# VCO_4046_with_low_pass_filter.net
KiCad netlist of a schematic drawn in EasyEDA
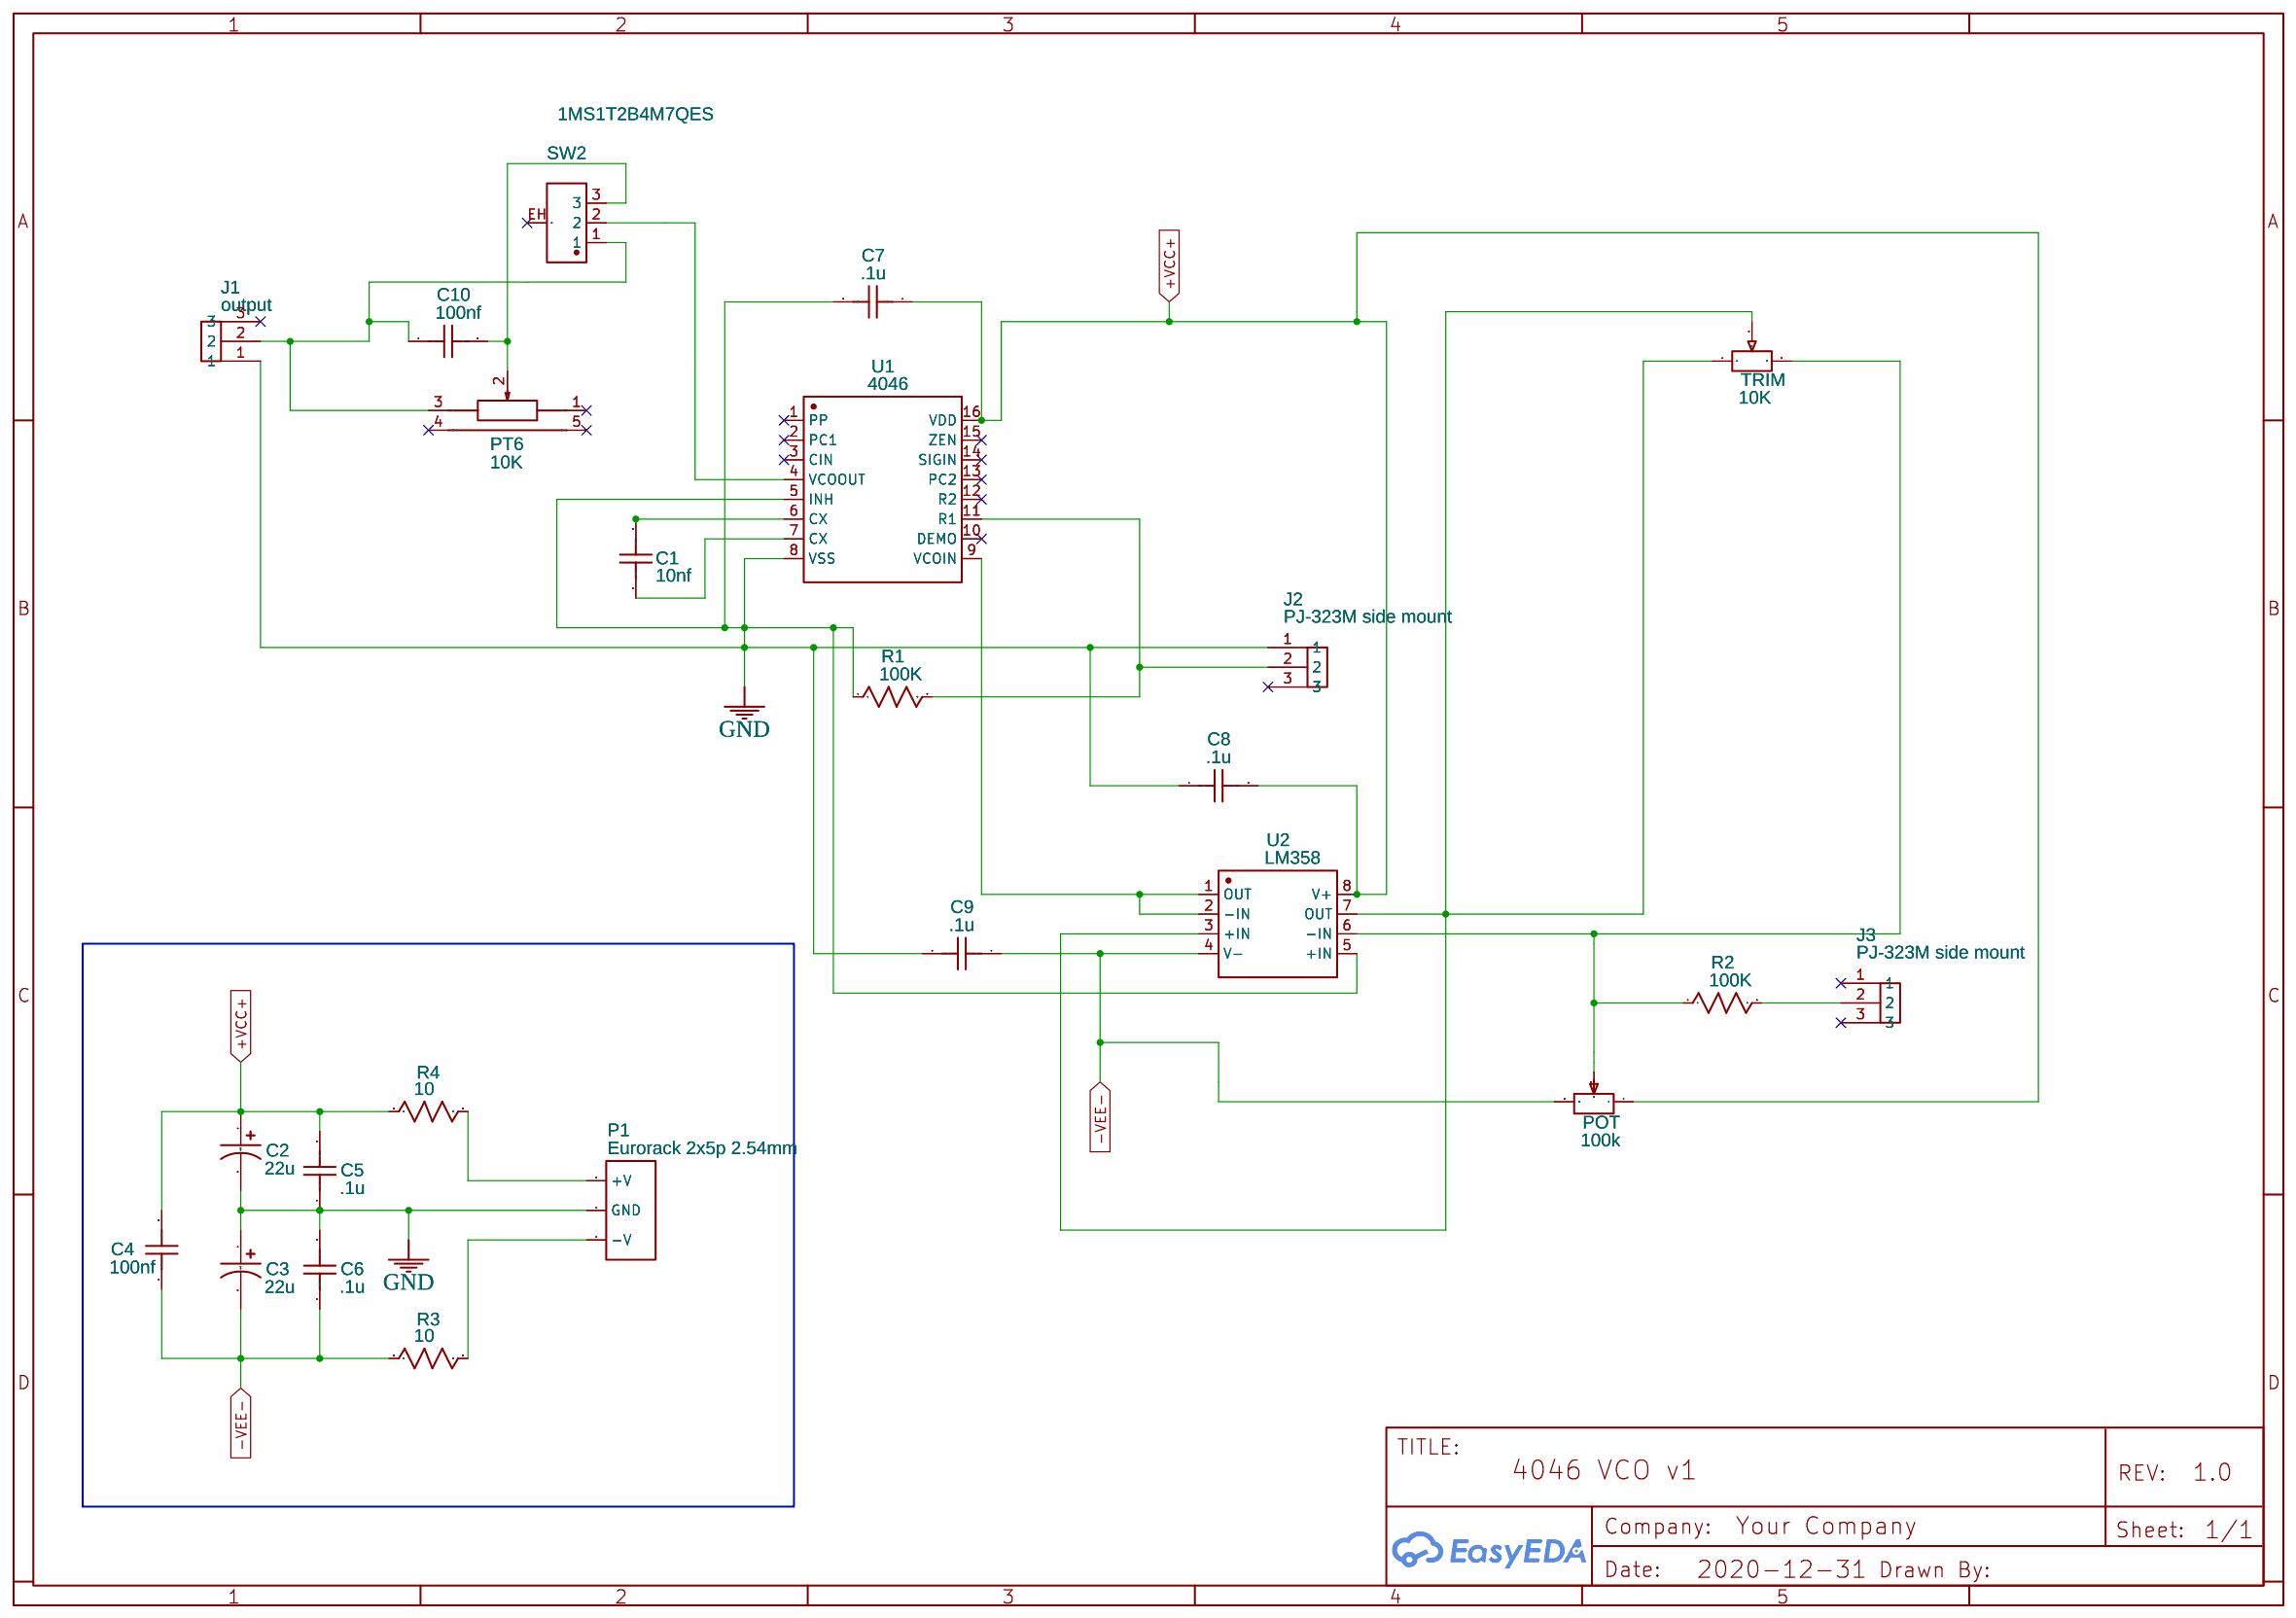
[diagram p0: schematic sheet]

(export (version "E")
  (design (tool "Eeschema 10.0.6"))
  (components
    (comp (ref "C1") (value "10nf") (libsource (lib "") (part "C_RAD-0.1_US")))
    (comp (ref "C2") (value "22u") (libsource (lib "") (part "CE_TH_D5.0×F2.0_US")))
    (comp (ref "C3") (value "22u") (libsource (lib "") (part "CE_TH_D5.0×F2.0_US")))
    (comp (ref "C4") (value "100nf") (libsource (lib "") (part "C_RAD-0.1_US")))
    (comp (ref "C5") (value ".1u") (libsource (lib "") (part "C_RAD-0.1_US")))
    (comp (ref "C6") (value ".1u") (libsource (lib "") (part "C_RAD-0.1_US")))
    (comp (ref "C7") (value ".1u") (libsource (lib "") (part "C_RAD-0.1_US_2")))
    (comp (ref "C8") (value ".1u") (libsource (lib "") (part "C_RAD-0.1_US_1")))
    (comp (ref "C9") (value ".1u") (libsource (lib "") (part "C_RAD-0.1_US_2")))
    (comp (ref "C10") (value "100nf") (libsource (lib "") (part "C_RAD-0.1_US_1")))
    (comp (ref "J1")
      (value "output")
      (fields (field (name "BOM_Manufacturer Part") "PJ-323M"))
      (libsource (lib "") (part "PJ-323M side mount"))
    )
    (comp (ref "J2")
      (value "PJ-323M side mount")
      (fields (field (name "BOM_Manufacturer Part") "PJ-323M"))
      (libsource (lib "") (part "PJ-323M side mount_1"))
    )
    (comp (ref "J3")
      (value "PJ-323M side mount")
      (fields (field (name "BOM_Manufacturer Part") "PJ-323M"))
      (libsource (lib "") (part "PJ-323M side mount_1"))
    )
    (comp (ref "P1")
      (value "Eurorack 2x5p 2.54mm")
      (fields
        (field (name "BOM_Manufacturer Part") "IDC Box 2.54mm 2X5P")
        (field (name "BOM_Supplier Part") "C5665")
      )
      (libsource (lib "") (part "Eurorack 2x5p 2.54mm"))
    )
    (comp (ref "POT")
      (value "100k")
      (fields
        (field (name "BOM_Manufacturer Part") "PTV09A-2020F-B103")
        (field (name "BOM_Supplier Part") "C370978")
      )
      (libsource (lib "") (part "RK1631110U1Q"))
    )
    (comp (ref "PT6")
      (value "10K")
      (fields
        (field (name "BOM_Manufacturer Part") "RK09K1110A0J")
        (field (name "BOM_Supplier Part") "C209767")
      )
      (libsource (lib "") (part "RK09K1110A0J"))
    )
    (comp (ref "R1") (value "100K") (libsource (lib "") (part "R_AXIAL-0.5_US")))
    (comp (ref "R2") (value "100K") (libsource (lib "") (part "R_AXIAL-0.5_US")))
    (comp (ref "R3") (value "10") (libsource (lib "") (part "R_AXIAL-0.5_US")))
    (comp (ref "R4") (value "10") (libsource (lib "") (part "R_AXIAL-0.5_US")))
    (comp (ref "SW2")
      (value "1MS1T2B4M7QES")
      (fields (field (name "BOM_Supplier Part") "C496157"))
      (libsource (lib "") (part "1MS1T2B4M7QES"))
    )
    (comp (ref "TRIM")
      (value "10K")
      (fields
        (field (name "BOM_Manufacturer Part") "3386P-1-103")
        (field (name "BOM_Supplier Part") "C118953")
      )
      (libsource (lib "") (part "3386P-1-103_C118953"))
    )
    (comp (ref "U1") (value "4046") (libsource (lib "") (part "4046")))
    (comp (ref "U2") (value "LM358") (libsource (lib "") (part "LM358")))
  )
  (nets
    (net (code "1") (name "+VCC+") (class "Default")
      (node (ref "C2") (pin "1") (pinfunction "1_1") (pintype "unspecified"))
      (node (ref "C4") (pin "2") (pinfunction "2_2") (pintype "unspecified"))
      (node (ref "C5") (pin "2") (pinfunction "2_2") (pintype "unspecified"))
      (node (ref "C7") (pin "1") (pinfunction "1_1") (pintype "unspecified"))
      (node (ref "C8") (pin "2") (pinfunction "2_2") (pintype "unspecified"))
      (node (ref "POT") (pin "1") (pinfunction "1_1") (pintype "input"))
      (node (ref "R4") (pin "1") (pinfunction "1_1") (pintype "unspecified"))
      (node (ref "U1") (pin "16") (pinfunction "VDD_16") (pintype "unspecified"))
      (node (ref "U2") (pin "8") (pinfunction "V+_8") (pintype "unspecified"))
    )
    (net (code "2") (name "-VEE-") (class "Default")
      (node (ref "C3") (pin "2") (pinfunction "2_2") (pintype "unspecified"))
      (node (ref "C4") (pin "1") (pinfunction "1_1") (pintype "unspecified"))
      (node (ref "C6") (pin "1") (pinfunction "1_1") (pintype "unspecified"))
      (node (ref "C9") (pin "1") (pinfunction "1_1") (pintype "unspecified"))
      (node (ref "POT") (pin "3") (pinfunction "3_3") (pintype "input"))
      (node (ref "R3") (pin "1") (pinfunction "1_1") (pintype "unspecified"))
      (node (ref "U2") (pin "4") (pinfunction "V-_4") (pintype "unspecified"))
    )
    (net (code "3") (name "GND") (class "Default")
      (node (ref "C2") (pin "2") (pinfunction "2_2") (pintype "unspecified"))
      (node (ref "C3") (pin "1") (pinfunction "1_1") (pintype "unspecified"))
      (node (ref "C5") (pin "1") (pinfunction "1_1") (pintype "unspecified"))
      (node (ref "C6") (pin "2") (pinfunction "2_2") (pintype "unspecified"))
      (node (ref "C7") (pin "2") (pinfunction "2_2") (pintype "unspecified"))
      (node (ref "C8") (pin "1") (pinfunction "1_1") (pintype "unspecified"))
      (node (ref "C9") (pin "2") (pinfunction "2_2") (pintype "unspecified"))
      (node (ref "J1") (pin "1") (pinfunction "1_1") (pintype "unspecified"))
      (node (ref "J2") (pin "1") (pinfunction "1_1") (pintype "unspecified"))
      (node (ref "P1") (pin "2") (pinfunction "GND_2") (pintype "unspecified"))
      (node (ref "R1") (pin "1") (pinfunction "1_1") (pintype "unspecified"))
      (node (ref "U1") (pin "5") (pinfunction "INH_5") (pintype "unspecified"))
      (node (ref "U1") (pin "8") (pinfunction "VSS_8") (pintype "unspecified"))
      (node (ref "U2") (pin "5") (pinfunction "+IN_5") (pintype "unspecified"))
    )
    (net (code "4") (name "Net-(C1-Pad1)") (class "Default")
      (node (ref "C1") (pin "1") (pinfunction "1_1") (pintype "unspecified"))
      (node (ref "U1") (pin "7") (pinfunction "CX_7") (pintype "unspecified"))
    )
    (net (code "5") (name "Net-(C1-Pad2)") (class "Default")
      (node (ref "C1") (pin "2") (pinfunction "2_2") (pintype "unspecified"))
      (node (ref "U1") (pin "6") (pinfunction "CX_6") (pintype "unspecified"))
    )
    (net (code "6") (name "Net-(C10-Pad1)") (class "Default")
      (node (ref "C10") (pin "1") (pinfunction "1_1") (pintype "unspecified"))
      (node (ref "J1") (pin "2") (pinfunction "2_2") (pintype "unspecified"))
      (node (ref "PT6") (pin "3") (pinfunction "3_3") (pintype "unspecified"))
      (node (ref "SW2") (pin "1") (pinfunction "1_1") (pintype "unspecified"))
    )
    (net (code "7") (name "Net-(C10-Pad2)") (class "Default")
      (node (ref "C10") (pin "2") (pinfunction "2_2") (pintype "unspecified"))
      (node (ref "PT6") (pin "2") (pinfunction "2_2") (pintype "unspecified"))
      (node (ref "SW2") (pin "3") (pinfunction "3_3") (pintype "unspecified"))
    )
    (net (code "8") (name "Net-(J3-Pad2)") (class "Default")
      (node (ref "J3") (pin "2") (pinfunction "2_2") (pintype "unspecified"))
      (node (ref "R2") (pin "2") (pinfunction "2_2") (pintype "unspecified"))
    )
    (net (code "9") (name "Net-(P1-+V)") (class "Default")
      (node (ref "P1") (pin "3") (pinfunction "+V_3") (pintype "unspecified"))
      (node (ref "R4") (pin "2") (pinfunction "2_2") (pintype "unspecified"))
    )
    (net (code "10") (name "Net-(P1--V)") (class "Default")
      (node (ref "P1") (pin "1") (pinfunction "-V_1") (pintype "unspecified"))
      (node (ref "R3") (pin "2") (pinfunction "2_2") (pintype "unspecified"))
    )
    (net (code "11") (name "Net-(POT-Pad2)") (class "Default")
      (node (ref "POT") (pin "2") (pinfunction "2_2") (pintype "input"))
      (node (ref "R2") (pin "1") (pinfunction "1_1") (pintype "unspecified"))
      (node (ref "TRIM") (pin "3") (pinfunction "3_3") (pintype "input"))
      (node (ref "U2") (pin "6") (pinfunction "-IN_6") (pintype "unspecified"))
    )
    (net (code "12") (name "Net-(TRIM-Pad1)") (class "Default")
      (node (ref "TRIM") (pin "1") (pinfunction "1_1") (pintype "input"))
      (node (ref "TRIM") (pin "2") (pinfunction "2_2") (pintype "input"))
      (node (ref "U2") (pin "3") (pinfunction "+IN_3") (pintype "unspecified"))
      (node (ref "U2") (pin "7") (pinfunction "OUT_7") (pintype "unspecified"))
    )
    (net (code "13") (name "Net-(U1-R1)") (class "Default")
      (node (ref "J2") (pin "2") (pinfunction "2_2") (pintype "unspecified"))
      (node (ref "R1") (pin "2") (pinfunction "2_2") (pintype "unspecified"))
      (node (ref "U1") (pin "11") (pinfunction "R1_11") (pintype "unspecified"))
    )
    (net (code "14") (name "Net-(U1-VCOIN)") (class "Default")
      (node (ref "U1") (pin "9") (pinfunction "VCOIN_9") (pintype "unspecified"))
      (node (ref "U2") (pin "1") (pinfunction "OUT_1") (pintype "unspecified"))
      (node (ref "U2") (pin "2") (pinfunction "-IN_2") (pintype "unspecified"))
    )
    (net (code "15") (name "Net-(U1-VCOOUT)") (class "Default")
      (node (ref "SW2") (pin "2") (pinfunction "2_2") (pintype "unspecified"))
      (node (ref "U1") (pin "4") (pinfunction "VCOOUT_4") (pintype "unspecified"))
    )
    (net (code "16") (name "unconnected-(J1-Pad3)") (class "Default")
      (node (ref "J1") (pin "3") (pinfunction "3_3") (pintype "unspecified+no_connect"))
    )
    (net (code "17") (name "unconnected-(J2-Pad3)") (class "Default")
      (node (ref "J2") (pin "3") (pinfunction "3_3") (pintype "unspecified+no_connect"))
    )
    (net (code "18") (name "unconnected-(J3-Pad1)") (class "Default")
      (node (ref "J3") (pin "1") (pinfunction "1_1") (pintype "unspecified+no_connect"))
    )
    (net (code "19") (name "unconnected-(J3-Pad3)") (class "Default")
      (node (ref "J3") (pin "3") (pinfunction "3_3") (pintype "unspecified+no_connect"))
    )
    (net (code "20") (name "unconnected-(PT6-EH-Pad4)") (class "Default")
      (node (ref "PT6") (pin "4") (pinfunction "EH_4") (pintype "unspecified+no_connect"))
    )
    (net (code "21") (name "unconnected-(PT6-EH-Pad5)") (class "Default")
      (node (ref "PT6") (pin "5") (pinfunction "EH_5") (pintype "unspecified+no_connect"))
    )
    (net (code "22") (name "unconnected-(PT6-Pad1)") (class "Default")
      (node (ref "PT6") (pin "1") (pinfunction "1_1") (pintype "unspecified+no_connect"))
    )
    (net (code "23") (name "unconnected-(SW2-PadEH)") (class "Default")
      (node (ref "SW2") (pin "EH") (pinfunction "EH_EH") (pintype "unspecified+no_connect"))
    )
    (net (code "24") (name "unconnected-(U1-CIN-Pad3)") (class "Default")
      (node (ref "U1") (pin "3") (pinfunction "CIN_3") (pintype "unspecified+no_connect"))
    )
    (net (code "25") (name "unconnected-(U1-DEMO-Pad10)") (class "Default")
      (node (ref "U1") (pin "10") (pinfunction "DEMO_10") (pintype "unspecified+no_connect"))
    )
    (net (code "26") (name "unconnected-(U1-PC1-Pad2)") (class "Default")
      (node (ref "U1") (pin "2") (pinfunction "PC1_2") (pintype "unspecified+no_connect"))
    )
    (net (code "27") (name "unconnected-(U1-PC2-Pad13)") (class "Default")
      (node (ref "U1") (pin "13") (pinfunction "PC2_13") (pintype "unspecified+no_connect"))
    )
    (net (code "28") (name "unconnected-(U1-PP-Pad1)") (class "Default")
      (node (ref "U1") (pin "1") (pinfunction "PP_1") (pintype "unspecified+no_connect"))
    )
    (net (code "29") (name "unconnected-(U1-R2-Pad12)") (class "Default")
      (node (ref "U1") (pin "12") (pinfunction "R2_12") (pintype "unspecified+no_connect"))
    )
    (net (code "30") (name "unconnected-(U1-SIGIN-Pad14)") (class "Default")
      (node (ref "U1") (pin "14") (pinfunction "SIGIN_14") (pintype "unspecified+no_connect"))
    )
    (net (code "31") (name "unconnected-(U1-ZEN-Pad15)") (class "Default")
      (node (ref "U1") (pin "15") (pinfunction "ZEN_15") (pintype "unspecified+no_connect"))
    )
  )
)
